# 2-PowerInput.net
KiCad netlist of a schematic drawn in Altium Designer
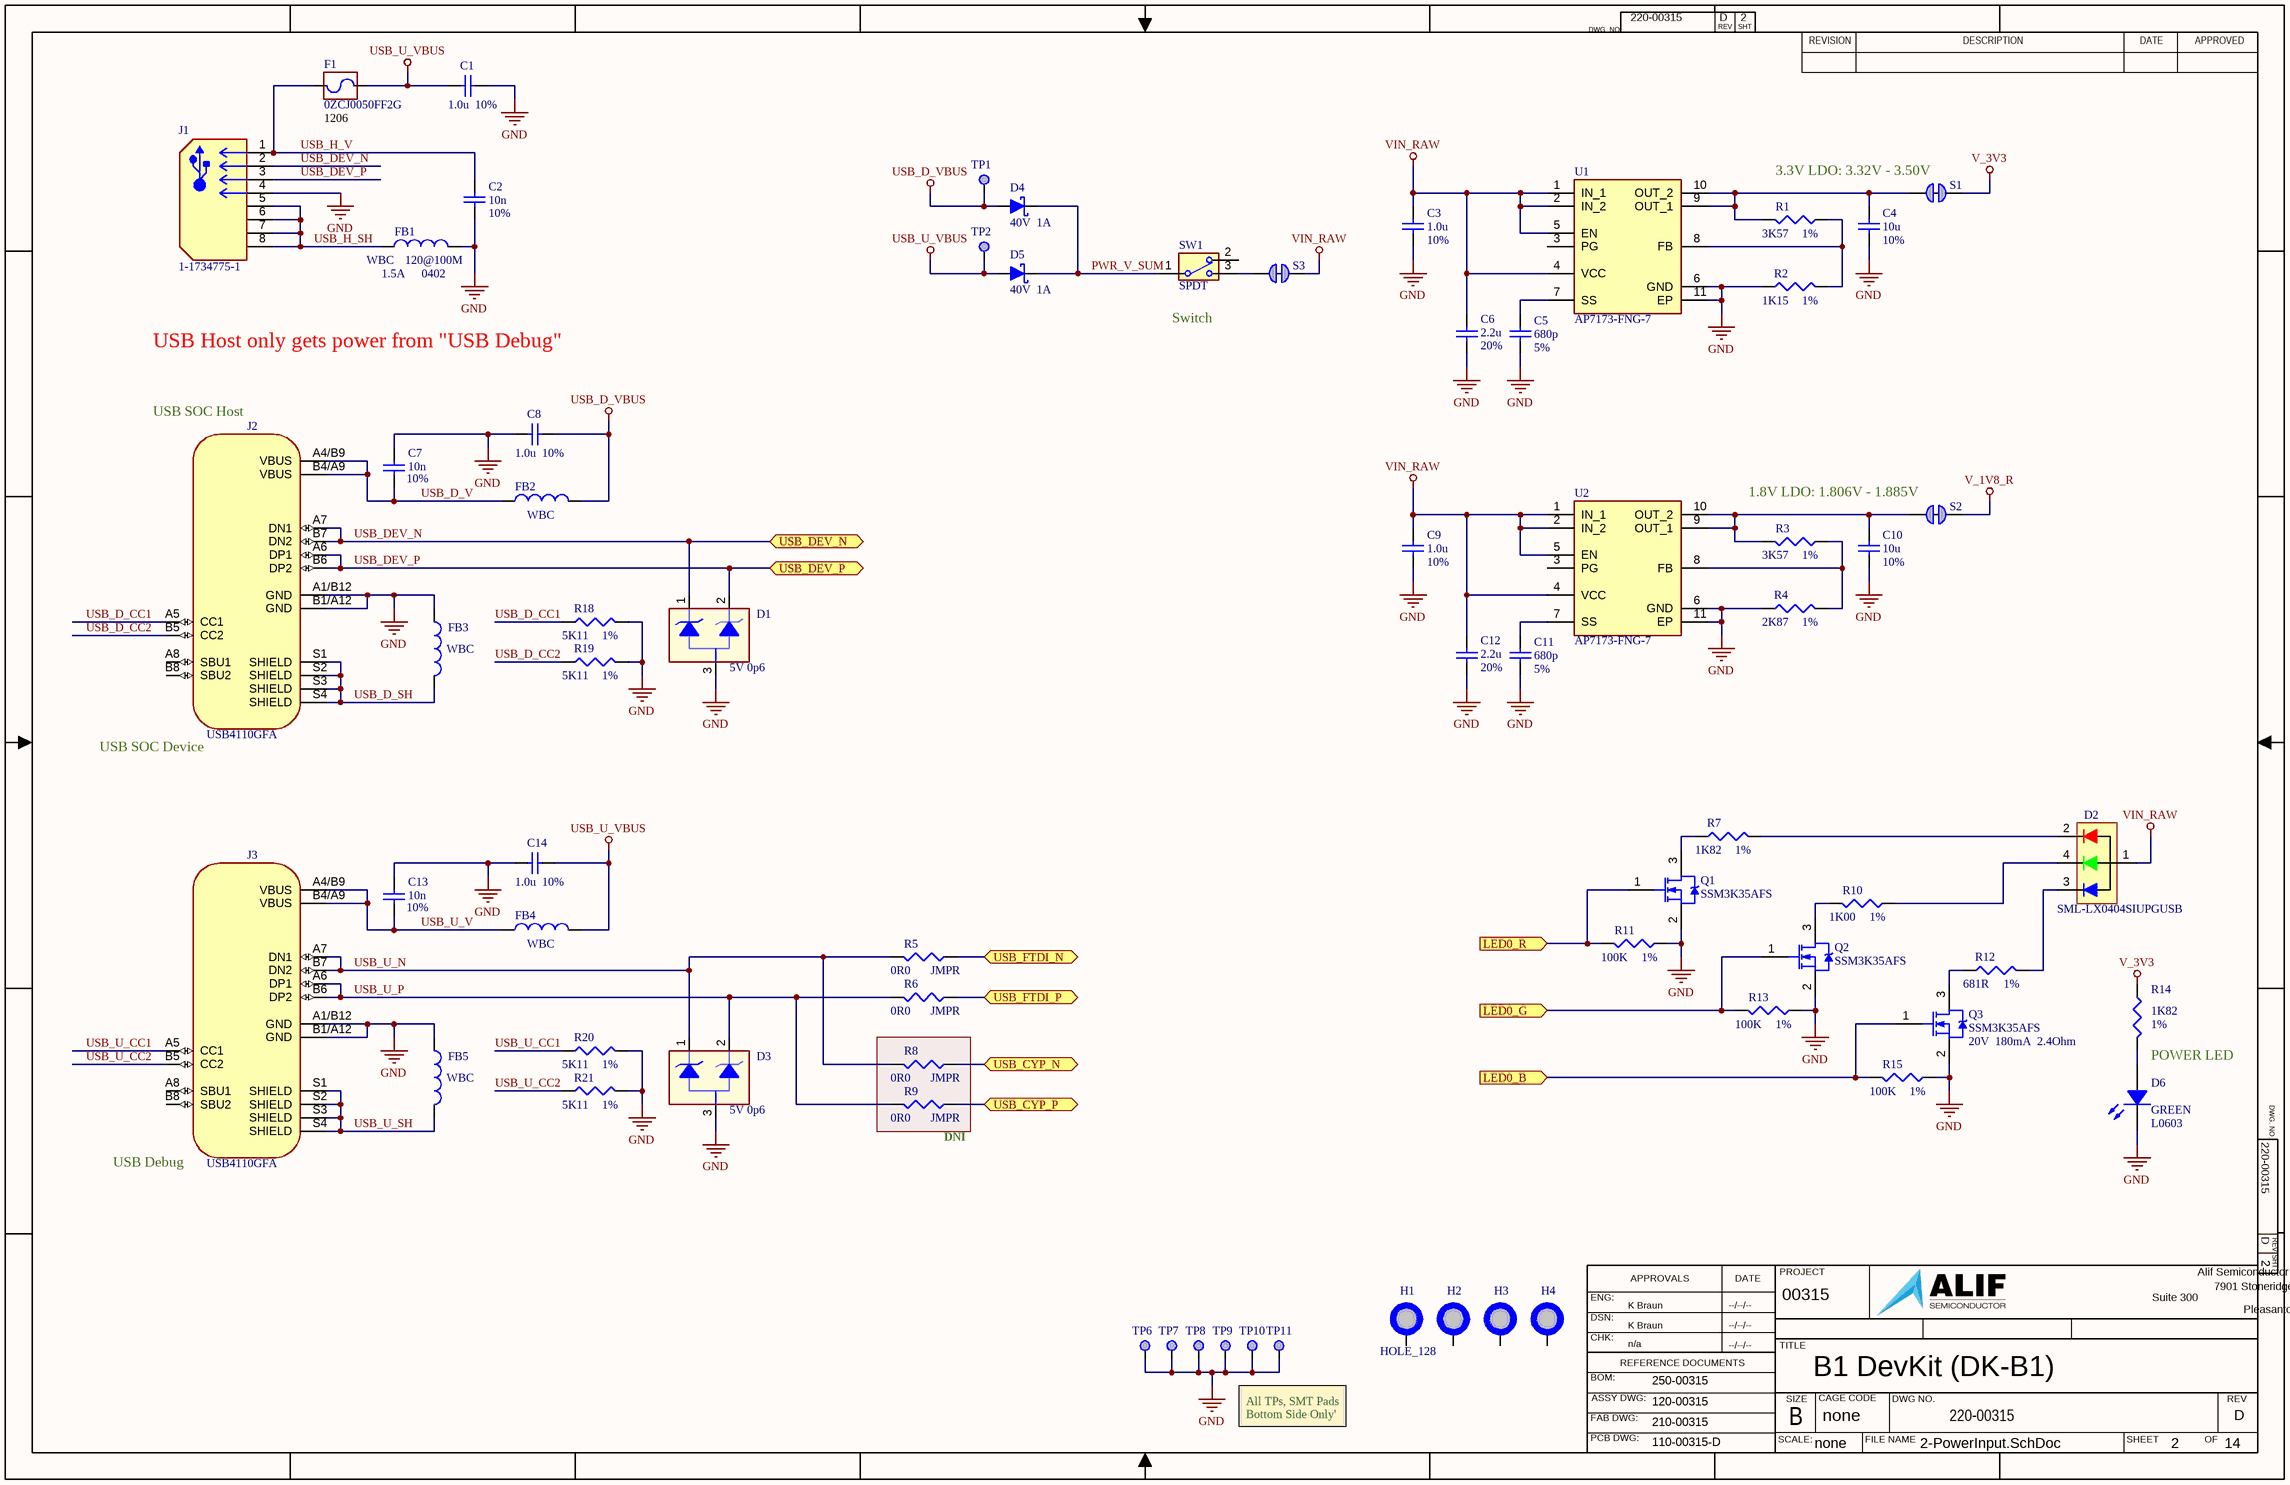
[diagram p0: 2-PowerInput.SchDoc]

(export (version "E")
  (design (tool "Eeschema 10.0.6"))
  (components
    (comp (ref "C1")
      (value "1.0u")
      (footprint "CAPC0402-01")
      (description "Cap,1.0uF,20%,25V,X5R,0402")
      (fields
        (field (name "VOLTAGE") "25V")
        (field (name "TOLERANCE") "10%")
        (field (name "Comment") "Cap")
        (field (name "PUBLISHER") "Altium Limited")
      )
      (libsource (lib "kb1") (part "Cap"))
    )
    (comp (ref "C2")
      (value "10n")
      (footprint "CAPC0402-01")
      (description "Cap,10nF,10%,50V,X7R,0402")
      (fields
        (field (name "VOLTAGE") "50V")
        (field (name "TOLERANCE") "10%")
        (field (name "Comment") "Cap")
        (field (name "PUBLISHER") "Altium Limited")
      )
      (libsource (lib "kb1") (part "Cap"))
    )
    (comp (ref "C3")
      (value "1.0u")
      (footprint "CAPC0402-01")
      (description "Cap,1.0uF,20%,25V,X5R,0402")
      (fields
        (field (name "VOLTAGE") "25V")
        (field (name "TOLERANCE") "10%")
        (field (name "Comment") "Cap")
        (field (name "PUBLISHER") "Altium Limited")
      )
      (libsource (lib "kb1") (part "Cap"))
    )
    (comp (ref "C4")
      (value "10u")
      (footprint "CAPC0402-01")
      (description "Cap,10uF,20%,10V,X5R,0402")
      (fields
        (field (name "VOLTAGE") "10V")
        (field (name "TOLERANCE") "10%")
        (field (name "Comment") "Cap")
        (field (name "PUBLISHER") "Altium Limited")
      )
      (libsource (lib "kb1") (part "Cap"))
    )
    (comp (ref "C5")
      (value "680p")
      (footprint "CAPC0402-01")
      (description "Cap,680pF,5%,50V,C0G,0402")
      (fields
        (field (name "VOLTAGE") "50V")
        (field (name "TOLERANCE") "5%")
        (field (name "Comment") "Cap")
        (field (name "PUBLISHER") "Altium Limited")
      )
      (libsource (lib "kb1") (part "Cap"))
    )
    (comp (ref "C6")
      (value "2.2u")
      (footprint "CAPC0402-01")
      (description "Cap,2.2uF,20%,25V,X5R,0402")
      (fields
        (field (name "VOLTAGE") "25V")
        (field (name "TOLERANCE") "20%")
        (field (name "Comment") "Cap_225M25VX5R0402_1")
        (field (name "PUBLISHER") "Altium Limited")
      )
      (libsource (lib "Alif-2") (part "Cap_225M25VX5R0402_1"))
    )
    (comp (ref "C7")
      (value "10n")
      (footprint "CAPC0402-01")
      (description "Cap,10nF,10%,50V,X7R,0402")
      (fields
        (field (name "VOLTAGE") "50V")
        (field (name "TOLERANCE") "10%")
        (field (name "Comment") "Cap")
        (field (name "PUBLISHER") "Altium Limited")
      )
      (libsource (lib "kb1") (part "Cap"))
    )
    (comp (ref "C8")
      (value "1.0u")
      (footprint "CAPC0402-01")
      (description "Cap,1.0uF,20%,25V,X5R,0402")
      (fields
        (field (name "VOLTAGE") "25V")
        (field (name "TOLERANCE") "10%")
        (field (name "Comment") "Cap")
        (field (name "PUBLISHER") "Altium Limited")
      )
      (libsource (lib "kb1") (part "Cap"))
    )
    (comp (ref "C9")
      (value "1.0u")
      (footprint "CAPC0402-01")
      (description "Cap,1.0uF,20%,25V,X5R,0402")
      (fields
        (field (name "VOLTAGE") "25V")
        (field (name "TOLERANCE") "10%")
        (field (name "Comment") "Cap")
        (field (name "PUBLISHER") "Altium Limited")
      )
      (libsource (lib "kb1") (part "Cap"))
    )
    (comp (ref "C10")
      (value "10u")
      (footprint "CAPC0402-01")
      (description "Cap,10uF,20%,10V,X5R,0402")
      (fields
        (field (name "VOLTAGE") "10V")
        (field (name "TOLERANCE") "10%")
        (field (name "Comment") "Cap")
        (field (name "PUBLISHER") "Altium Limited")
      )
      (libsource (lib "kb1") (part "Cap"))
    )
    (comp (ref "C11")
      (value "680p")
      (footprint "CAPC0402-01")
      (description "Cap,680pF,5%,50V,C0G,0402")
      (fields
        (field (name "VOLTAGE") "50V")
        (field (name "TOLERANCE") "5%")
        (field (name "Comment") "Cap")
        (field (name "PUBLISHER") "Altium Limited")
      )
      (libsource (lib "kb1") (part "Cap"))
    )
    (comp (ref "C12")
      (value "2.2u")
      (footprint "CAPC0402-01")
      (description "Cap,2.2uF,20%,25V,X5R,0402")
      (fields
        (field (name "VOLTAGE") "25V")
        (field (name "TOLERANCE") "20%")
        (field (name "Comment") "Cap_225M25VX5R0402_1")
        (field (name "PUBLISHER") "Altium Limited")
      )
      (libsource (lib "Alif-2") (part "Cap_225M25VX5R0402_1"))
    )
    (comp (ref "C13")
      (value "10n")
      (footprint "CAPC0402-01")
      (description "Cap,10nF,10%,50V,X7R,0402")
      (fields
        (field (name "VOLTAGE") "50V")
        (field (name "TOLERANCE") "10%")
        (field (name "Comment") "Cap")
        (field (name "PUBLISHER") "Altium Limited")
      )
      (libsource (lib "kb1") (part "Cap"))
    )
    (comp (ref "C14")
      (value "1.0u")
      (footprint "CAPC0402-01")
      (description "Cap,1.0uF,20%,25V,X5R,0402")
      (fields
        (field (name "VOLTAGE") "25V")
        (field (name "TOLERANCE") "10%")
        (field (name "Comment") "Cap")
        (field (name "PUBLISHER") "Altium Limited")
      )
      (libsource (lib "kb1") (part "Cap"))
    )
    (comp (ref "D1")
      (value "5V 0p6")
      (footprint "SOT-23_DBZ_TEX")
      (description "Diode,Zener,Dual,Common Anode")
      (fields (field (name "Comment") "Zener") (field (name "PUBLISHER") "Altium Limited"))
      (libsource (lib "Alif-2") (part "D Zener_2_ComA"))
    )
    (comp (ref "D2")
      (value "SML-LX0404SIUPGUSB")
      (footprint "LED_SML-LX0404_LUM")
      (description "Diode,LED,RGB, (@2mA) -> R=10mcd & 1.75V, G = 50mcd & 2.75V, B = 20mcd & 2.95V, 0404(1mm x 1mm)")
      (fields (field (name "PUBLISHER") "Altium Limited"))
      (libsource (lib "Alif-2") (part "D LED_RGB_CA_1MMc1MM"))
    )
    (comp (ref "D3")
      (value "5V 0p6")
      (footprint "SOT-23_DBZ_TEX")
      (description "Diode,Zener,Dual,Common Anode")
      (fields (field (name "Comment") "Zener") (field (name "PUBLISHER") "Altium Limited"))
      (libsource (lib "Alif-2") (part "D Zener_2_ComA"))
    )
    (comp (ref "D4")
      (value "40V  1A")
      (footprint "SOD123F_NXP")
      (description "Diode,Schottky,1A,40V,SOD123")
      (fields (field (name "Comment") "D Schottky") (field (name "PUBLISHER") "Altium Limited"))
      (libsource (lib "Alif-2") (part "D Schottky"))
    )
    (comp (ref "D5")
      (value "40V  1A")
      (footprint "SOD123F_NXP")
      (description "Diode,Schottky,1A,40V,SOD123")
      (fields (field (name "Comment") "D Schottky") (field (name "PUBLISHER") "Altium Limited"))
      (libsource (lib "Alif-2") (part "D Schottky"))
    )
    (comp (ref "D6")
      (value "GREEN")
      (footprint "LED_0603-GRN_AK")
      (description "Diode,LED,Green 573nm,300mcd @ 20mA,0603")
      (fields
        (field (name "PACKAGEREFERENCE") "L0603")
        (field (name "Comment") "D LED2")
        (field (name "PUBLISHER") "Altium Limited")
      )
      (libsource (lib "Alif-2") (part "D LED2"))
    )
    (comp (ref "F1")
      (value "0ZCJ0050FF2G")
      (footprint "1206")
      (description "Fuse,Poly PTC,1A,8V,150mOhm,1206")
      (fields (field (name "COPYRIGHT") "Copyright (C) 2022 Ultra Librarian. All rights reserved."))
      (libsource (lib "Alif-2") (part "Fuse_PTC_0ZCJ0050FF2G"))
    )
    (comp (ref "FB1")
      (value "WBC")
      (footprint "FB_0402_MuRata_as_R0402")
      (description "Ind,WidebandChoke,1.5A,120ohm@100MHz,95mOhm,0402")
      (fields
        (field (name "TOLERANCE") "30%")
        (field (name "IMPEDANCE") "120@100M")
        (field (name "PCB_FOOTPRINT") "0402")
        (field (name "RMS_CURRENT") "1.5A")
        (field (name "Comment") "Ind_WBC_1A5_120@100M0402_1")
        (field (name "PUBLISHER") "Altium Limited")
      )
      (libsource (lib "Alif2") (part "Ind_WBC_1A5_120@100M0402_1"))
    )
    (comp (ref "FB2")
      (value "WBC")
      (footprint "FB_0402_MuRata_as_R0402")
      (description "Ind,WidebandChoke,1.5A,120ohm@100MHz,95mOhm,0402")
      (fields
        (field (name "TOLERANCE") "30%")
        (field (name "Comment") "Ind_WBC_1A5_120@100M0402_1")
        (field (name "PUBLISHER") "Altium Limited")
      )
      (libsource (lib "Alif2") (part "Ind_WBC_1A5_120@100M0402_1"))
    )
    (comp (ref "FB3")
      (value "WBC")
      (footprint "FB_0402_MuRata_as_R0402")
      (description "Ind,WidebandChoke,1.5A,120ohm@100MHz,95mOhm,0402")
      (fields
        (field (name "TOLERANCE") "30%")
        (field (name "Comment") "Ind_WBC_1A5_120@100M0402_1")
        (field (name "PUBLISHER") "Altium Limited")
      )
      (libsource (lib "Alif2") (part "Ind_WBC_1A5_120@100M0402_1"))
    )
    (comp (ref "FB4")
      (value "WBC")
      (footprint "FB_0402_MuRata_as_R0402")
      (description "Ind,WidebandChoke,1.5A,120ohm@100MHz,95mOhm,0402")
      (fields
        (field (name "TOLERANCE") "30%")
        (field (name "Comment") "Ind_WBC_1A5_120@100M0402_1")
        (field (name "PUBLISHER") "Altium Limited")
      )
      (libsource (lib "Alif2") (part "Ind_WBC_1A5_120@100M0402_1"))
    )
    (comp (ref "FB5")
      (value "WBC")
      (footprint "FB_0402_MuRata_as_R0402")
      (description "Ind,WidebandChoke,1.5A,120ohm@100MHz,95mOhm,0402")
      (fields
        (field (name "TOLERANCE") "30%")
        (field (name "Comment") "Ind_WBC_1A5_120@100M0402_1")
        (field (name "PUBLISHER") "Altium Limited")
      )
      (libsource (lib "Alif2") (part "Ind_WBC_1A5_120@100M0402_1"))
    )
    (comp (ref "H1")
      (value "HOLE_128")
      (footprint "Hole_#4")
      (description "Hole, #4,--not a BOM item--")
      (libsource (lib "Alif-2") (part "HOLE_128"))
    )
    (comp (ref "H2")
      (value "HOLE_128")
      (footprint "Hole_#4")
      (description "Hole, #4,--not a BOM item--")
      (libsource (lib "Alif-2") (part "HOLE_128"))
    )
    (comp (ref "H3")
      (value "HOLE_128")
      (footprint "Hole_#4")
      (description "Hole, #4,--not a BOM item--")
      (libsource (lib "Alif-2") (part "HOLE_128"))
    )
    (comp (ref "H4")
      (value "HOLE_128")
      (footprint "Hole_#4")
      (description "Hole, #4,--not a BOM item--")
      (libsource (lib "Alif-2") (part "HOLE_128"))
    )
    (comp (ref "J1")
      (value "1-1734775-1")
      (footprint "614004134726")
      (description "Conn,USB 2.0, Type A Recept,4 Pos, R/A")
      (fields (field (name "COPYRIGHT") "Copyright (C) 2022 Ultra Librarian. All rights reserved."))
      (libsource (lib "Alif-2") (part "Conn_1-1734775-1"))
    )
    (comp (ref "J2")
      (value "USB4110GFA")
      (footprint "CONN_USB_C_GCT_USB4110GFA")
      (description "CONN,USB-C, USB 2.0 Receptacle Connector 24 (16+8 Dummy) Position Surface Mount, Right Angle")
      (libsource (lib "Alif-2") (part "CONN_USB_C_SMT_USB4110GFA"))
    )
    (comp (ref "J3")
      (value "USB4110GFA")
      (footprint "CONN_USB_C_GCT_USB4110GFA")
      (description "CONN,USB-C, USB 2.0 Receptacle Connector 24 (16+8 Dummy) Position Surface Mount, Right Angle")
      (libsource (lib "Alif-2") (part "CONN_USB_C_SMT_USB4110GFA"))
    )
    (comp (ref "Q1")
      (value "NMOS-2_SOT")
      (footprint "SC75_SSM_TOS-L")
      (description "MOSFET,N-CH,20V,250mA,1.1Ohm,SOT-23")
      (fields
        (field (name "MANUFACTURER PART NUMBER 1") "SSM3K35AFS")
        (field (name "PUBLISHER") "Altium Limited")
      )
      (libsource (lib "Alif-2") (part "NMOS-2_SOT"))
    )
    (comp (ref "Q2")
      (value "NMOS-2_SOT")
      (footprint "SC75_SSM_TOS-L")
      (description "MOSFET,N-CH,20V,250mA,1.1Ohm,SOT-23")
      (fields
        (field (name "MANUFACTURER PART NUMBER 1") "SSM3K35AFS")
        (field (name "PUBLISHER") "Altium Limited")
      )
      (libsource (lib "Alif-2") (part "NMOS-2_SOT"))
    )
    (comp (ref "Q3")
      (value "20V  180mA  2.4Ohm")
      (footprint "SC75_SSM_TOS-L")
      (description "MOSFET,N-CH,20V,250mA,1.1Ohm,SOT-23")
      (fields
        (field (name "MANUFACTURER PART NUMBER 1") "SSM3K35AFS")
        (field (name "Comment") "NMOS-2_SOT")
        (field (name "PUBLISHER") "Altium Limited")
      )
      (libsource (lib "Alif-2") (part "NMOS-2_SOT"))
    )
    (comp (ref "R1")
      (value "3K57")
      (footprint "RESC0402-01")
      (description "Res,3K57,1%,100ppm,0402")
      (fields
        (field (name "TOLERANCE") "1%")
        (field (name "Comment") "Res3")
        (field (name "PUBLISHER") "Altium Limited")
      )
      (libsource (lib "kb1") (part "Res3"))
    )
    (comp (ref "R2")
      (value "1K15")
      (footprint "RESC0402-01")
      (description "Res,1K15,1%,100ppm,0402")
      (fields
        (field (name "TOLERANCE") "1%")
        (field (name "Comment") "Res3")
        (field (name "PUBLISHER") "Altium Limited")
      )
      (libsource (lib "kb1") (part "Res3"))
    )
    (comp (ref "R3")
      (value "3K57")
      (footprint "RESC0402-01")
      (description "Res,3K57,1%,100ppm,0402")
      (fields
        (field (name "TOLERANCE") "1%")
        (field (name "Comment") "Res3")
        (field (name "PUBLISHER") "Altium Limited")
      )
      (libsource (lib "kb1") (part "Res3"))
    )
    (comp (ref "R4")
      (value "2K87")
      (footprint "RESC0402-01")
      (description "Res,2K87,1%,100ppm,0402")
      (fields
        (field (name "TOLERANCE") "1%")
        (field (name "Comment") "Res3")
        (field (name "PUBLISHER") "Altium Limited")
      )
      (libsource (lib "kb1") (part "Res3"))
    )
    (comp (ref "R5")
      (value "0R0")
      (footprint "RESC0402-01")
      (description "Res,0R ohm,Jumper,0402")
      (fields
        (field (name "TOLERANCE") "JMPR")
        (field (name "Comment") "Res3")
        (field (name "PUBLISHER") "Altium Limited")
      )
      (libsource (lib "kb1") (part "Res3"))
    )
    (comp (ref "R6")
      (value "0R0")
      (footprint "RESC0402-01")
      (description "Res,0R ohm,Jumper,0402")
      (fields
        (field (name "TOLERANCE") "JMPR")
        (field (name "Comment") "Res3")
        (field (name "PUBLISHER") "Altium Limited")
      )
      (libsource (lib "kb1") (part "Res3"))
    )
    (comp (ref "R7")
      (value "1K82")
      (footprint "RESC0402-01")
      (description "Res,1K82,1%,100ppm,0402")
      (fields
        (field (name "TOLERANCE") "1%")
        (field (name "Comment") "Res3")
        (field (name "PUBLISHER") "Altium Limited")
      )
      (libsource (lib "kb1") (part "Res3"))
    )
    (comp (ref "R8")
      (value "0R0")
      (footprint "RESC0402-01")
      (description "DNI,Res,0R ohm,Jumper,0402")
      (fields
        (field (name "TOLERANCE") "JMPR")
        (field (name "Comment") "Res3")
        (field (name "PUBLISHER") "Altium Limited")
      )
      (libsource (lib "kb1") (part "Res3"))
    )
    (comp (ref "R9")
      (value "0R0")
      (footprint "RESC0402-01")
      (description "DNI,Res,0R ohm,Jumper,0402")
      (fields
        (field (name "TOLERANCE") "JMPR")
        (field (name "Comment") "Res3")
        (field (name "PUBLISHER") "Altium Limited")
      )
      (libsource (lib "kb1") (part "Res3"))
    )
    (comp (ref "R10")
      (value "1K00")
      (footprint "RESC0402-01")
      (description "Res,1K00,1%,100ppm,0402")
      (fields
        (field (name "TOLERANCE") "1%")
        (field (name "Comment") "Res3")
        (field (name "PUBLISHER") "Altium Limited")
      )
      (libsource (lib "kb1") (part "Res3"))
    )
    (comp (ref "R11")
      (value "100K")
      (footprint "RESC0402-01")
      (description "Res,100K,1%,100ppm,0402")
      (fields
        (field (name "TOLERANCE") "1%")
        (field (name "Comment") "Res3")
        (field (name "PUBLISHER") "Altium Limited")
      )
      (libsource (lib "kb1") (part "Res3"))
    )
    (comp (ref "R12")
      (value "681R")
      (footprint "RESC0402-01")
      (description "Res,681R,1%,100ppm,0402")
      (fields
        (field (name "TOLERANCE") "1%")
        (field (name "Comment") "Res3")
        (field (name "PUBLISHER") "Altium Limited")
      )
      (libsource (lib "kb1") (part "Res3"))
    )
    (comp (ref "R13")
      (value "100K")
      (footprint "RESC0402-01")
      (description "Res,100K,1%,100ppm,0402")
      (fields
        (field (name "TOLERANCE") "1%")
        (field (name "Comment") "Res3")
        (field (name "PUBLISHER") "Altium Limited")
      )
      (libsource (lib "kb1") (part "Res3"))
    )
    (comp (ref "R14")
      (value "1K82")
      (footprint "RESC0402-01")
      (description "Res,1K82,1%,100ppm,0402")
      (fields
        (field (name "TOLERANCE") "1%")
        (field (name "Comment") "Res3")
        (field (name "PUBLISHER") "Altium Limited")
      )
      (libsource (lib "kb1") (part "Res3"))
    )
    (comp (ref "R15")
      (value "100K")
      (footprint "RESC0402-01")
      (description "Res,100K,1%,100ppm,0402")
      (fields
        (field (name "TOLERANCE") "1%")
        (field (name "Comment") "Res3")
        (field (name "PUBLISHER") "Altium Limited")
      )
      (libsource (lib "kb1") (part "Res3"))
    )
    (comp (ref "R18")
      (value "5K11")
      (footprint "RESC0402-01")
      (description "Res,5K11,1%,100ppm,0402")
      (fields
        (field (name "TOLERANCE") "1%")
        (field (name "Comment") "Res3")
        (field (name "PUBLISHER") "Altium Limited")
      )
      (libsource (lib "kb1") (part "Res3"))
    )
    (comp (ref "R19")
      (value "5K11")
      (footprint "RESC0402-01")
      (description "Res,5K11,1%,100ppm,0402")
      (fields
        (field (name "TOLERANCE") "1%")
        (field (name "Comment") "Res3")
        (field (name "PUBLISHER") "Altium Limited")
      )
      (libsource (lib "kb1") (part "Res3"))
    )
    (comp (ref "R20")
      (value "5K11")
      (footprint "RESC0402-01")
      (description "Res,5K11,1%,100ppm,0402")
      (fields
        (field (name "TOLERANCE") "1%")
        (field (name "Comment") "Res3")
        (field (name "PUBLISHER") "Altium Limited")
      )
      (libsource (lib "kb1") (part "Res3"))
    )
    (comp (ref "R21")
      (value "5K11")
      (footprint "RESC0402-01")
      (description "Res,5K11,1%,100ppm,0402")
      (fields
        (field (name "TOLERANCE") "1%")
        (field (name "Comment") "Res3")
        (field (name "PUBLISHER") "Altium Limited")
      )
      (libsource (lib "kb1") (part "Res3"))
    )
    (comp (ref "S1")
      (value "SolderJumperShorted_Small")
      (footprint "Solderbridge_Shorted")
      (description "DNI,Solderable Jumper,Shorted")
      (fields (field (name "PUBLISHER") "Altium Limited"))
      (libsource (lib "Alif-2") (part "SolderJumperShorted_Small"))
    )
    (comp (ref "S2")
      (value "SolderJumperShorted_Small")
      (footprint "Solderbridge_Shorted")
      (description "DNI,Solderable Jumper,Shorted")
      (fields (field (name "PUBLISHER") "Altium Limited"))
      (libsource (lib "Alif-2") (part "SolderJumperShorted_Small"))
    )
    (comp (ref "S3")
      (value "SolderJumperShorted_Small")
      (footprint "Solderbridge_Shorted")
      (description "DNI,Solderable Jumper,Shorted")
      (fields (field (name "PUBLISHER") "Altium Limited"))
      (libsource (lib "Alif-2") (part "SolderJumperShorted_Small"))
    )
    (comp (ref "SW1")
      (value "SPDT")
      (footprint "SW_450301014042_WRE")
      (description "Switch,SPDT, 12V, 500mA, Non-Shorting, 3 Pin PCB Vertical")
      (fields (field (name "PUBLISHER") "Altium Limited"))
      (libsource (lib "Alif-2") (part "SW-SPDT_Vert-3P"))
    )
    (comp (ref "TP1")
      (value "TP_SMPAD")
      (footprint "TP_30_RND")
      (description "Test Point, SMT Pad,--not a BOM item--")
      (libsource (lib "Alif-2") (part "TP_SMPAD"))
    )
    (comp (ref "TP2")
      (value "TP_SMPAD")
      (footprint "TP_30_RND")
      (description "Test Point, SMT Pad,--not a BOM item--")
      (libsource (lib "Alif-2") (part "TP_SMPAD"))
    )
    (comp (ref "TP6")
      (value "TP_SMPAD")
      (footprint "TP_30_RND")
      (description "Test Point, SMT Pad,--not a BOM item--")
      (libsource (lib "Alif-2") (part "TP_SMPAD"))
    )
    (comp (ref "TP7")
      (value "TP_SMPAD")
      (footprint "TP_30_RND")
      (description "Test Point, SMT Pad,--not a BOM item--")
      (libsource (lib "Alif-2") (part "TP_SMPAD"))
    )
    (comp (ref "TP8")
      (value "TP_SMPAD")
      (footprint "TP_30_RND")
      (description "Test Point, SMT Pad,--not a BOM item--")
      (libsource (lib "Alif-2") (part "TP_SMPAD"))
    )
    (comp (ref "TP9")
      (value "TP_SMPAD")
      (footprint "TP_30_RND")
      (description "Test Point, SMT Pad,--not a BOM item--")
      (libsource (lib "Alif-2") (part "TP_SMPAD"))
    )
    (comp (ref "TP10")
      (value "TP_SMPAD")
      (footprint "TP_30_RND")
      (description "Test Point, SMT Pad,--not a BOM item--")
      (libsource (lib "Alif-2") (part "TP_SMPAD"))
    )
    (comp (ref "TP11")
      (value "TP_SMPAD")
      (footprint "TP_30_RND")
      (description "Test Point, SMT Pad,--not a BOM item--")
      (libsource (lib "Alif-2") (part "TP_SMPAD"))
    )
    (comp (ref "U1")
      (value "AP7173-FNG-7")
      (footprint "UDFN3030-10_SON50P300X300X63-11N")
      (description "IC, LDO,Adj 0.8V - 3.3V,1.5A,UDFN3030-10")
      (libsource (lib "Alif-2") (part "IC_LDO_AP7173-FNG-7"))
    )
    (comp (ref "U2")
      (value "AP7173-FNG-7")
      (footprint "UDFN3030-10_SON50P300X300X63-11N")
      (description "IC, LDO,Adj 0.8V - 3.3V,1.5A,UDFN3030-10")
      (libsource (lib "Alif-2") (part "IC_LDO_AP7173-FNG-7"))
    )
  )
  (nets
    (net (code "1") (name "/LED0_B") (class "Default")
      (node (ref "Q3") (pin "1") (pinfunction "G_1") (pintype "passive"))
      (node (ref "R15") (pin "2") (pinfunction "2_2") (pintype "passive"))
    )
    (net (code "2") (name "/LED0_G") (class "Default")
      (node (ref "Q2") (pin "1") (pinfunction "G_1") (pintype "passive"))
      (node (ref "R13") (pin "2") (pinfunction "2_2") (pintype "passive"))
    )
    (net (code "3") (name "/LED0_R") (class "Default")
      (node (ref "Q1") (pin "1") (pinfunction "G_1") (pintype "passive"))
      (node (ref "R11") (pin "2") (pinfunction "2_2") (pintype "passive"))
    )
    (net (code "4") (name "/PWR_V_SUM") (class "Default")
      (node (ref "D4") (pin "1") (pinfunction "K_1") (pintype "passive"))
      (node (ref "D5") (pin "1") (pinfunction "K_1") (pintype "passive"))
      (node (ref "SW1") (pin "1") (pinfunction "COMMON_1") (pintype "passive"))
    )
    (net (code "5") (name "/USB_CYP_N") (class "Default")
      (node (ref "R8") (pin "1") (pinfunction "1_1") (pintype "passive"))
    )
    (net (code "6") (name "/USB_CYP_P") (class "Default")
      (node (ref "R9") (pin "1") (pinfunction "1_1") (pintype "passive"))
    )
    (net (code "7") (name "/USB_DEV_N") (class "Default")
      (node (ref "D1") (pin "1") (pinfunction "K1_1") (pintype "passive"))
      (node (ref "J1") (pin "2") (pinfunction "2_2") (pintype "passive"))
      (node (ref "J2") (pin "A7") (pinfunction "DN1_A7") (pintype "bidirectional"))
      (node (ref "J2") (pin "B7") (pinfunction "DN2_B7") (pintype "bidirectional"))
    )
    (net (code "8") (name "/USB_DEV_P") (class "Default")
      (node (ref "D1") (pin "2") (pinfunction "2_2") (pintype "passive"))
      (node (ref "J1") (pin "3") (pinfunction "3_3") (pintype "passive"))
      (node (ref "J2") (pin "A6") (pinfunction "DP1_A6") (pintype "bidirectional"))
      (node (ref "J2") (pin "B6") (pinfunction "DP2_B6") (pintype "bidirectional"))
    )
    (net (code "9") (name "/USB_D_CC1") (class "Default")
      (node (ref "J2") (pin "A5") (pinfunction "CC1_A5") (pintype "bidirectional"))
      (node (ref "R18") (pin "1") (pinfunction "1_1") (pintype "passive"))
    )
    (net (code "10") (name "/USB_D_CC2") (class "Default")
      (node (ref "J2") (pin "B5") (pinfunction "CC2_B5") (pintype "bidirectional"))
      (node (ref "R19") (pin "1") (pinfunction "1_1") (pintype "passive"))
    )
    (net (code "11") (name "/USB_D_SH") (class "Default")
      (node (ref "FB3") (pin "2") (pinfunction "2_2") (pintype "passive"))
      (node (ref "J2") (pin "S1") (pinfunction "SHIELD_S1") (pintype "power_in"))
      (node (ref "J2") (pin "S2") (pinfunction "SHIELD_S2") (pintype "power_in"))
      (node (ref "J2") (pin "S3") (pinfunction "SHIELD_S3") (pintype "power_in"))
      (node (ref "J2") (pin "S4") (pinfunction "SHIELD_S4") (pintype "power_in"))
    )
    (net (code "12") (name "/USB_D_V") (class "Default")
      (node (ref "C7") (pin "2") (pinfunction "2_2") (pintype "passive"))
      (node (ref "FB2") (pin "1") (pinfunction "1_1") (pintype "passive"))
      (node (ref "J2") (pin "A4/B9") (pinfunction "VBUS_A4/B9") (pintype "power_in"))
      (node (ref "J2") (pin "B4/A9") (pinfunction "VBUS_B4/A9") (pintype "power_in"))
    )
    (net (code "13") (name "/USB_FTDI_N") (class "Default")
      (node (ref "R5") (pin "1") (pinfunction "1_1") (pintype "passive"))
    )
    (net (code "14") (name "/USB_FTDI_P") (class "Default")
      (node (ref "R6") (pin "1") (pinfunction "1_1") (pintype "passive"))
    )
    (net (code "15") (name "/USB_H_SH") (class "Default")
      (node (ref "FB1") (pin "1") (pinfunction "1_1") (pintype "passive"))
      (node (ref "J1") (pin "5") (pinfunction "5_5") (pintype "passive"))
      (node (ref "J1") (pin "6") (pinfunction "6_6") (pintype "passive"))
      (node (ref "J1") (pin "7") (pinfunction "7_7") (pintype "passive"))
      (node (ref "J1") (pin "8") (pinfunction "8_8") (pintype "passive"))
    )
    (net (code "16") (name "/USB_H_V") (class "Default")
      (node (ref "C2") (pin "2") (pinfunction "2_2") (pintype "passive"))
      (node (ref "F1") (pin "1") (pinfunction "1_1") (pintype "passive"))
      (node (ref "J1") (pin "1") (pinfunction "1_1") (pintype "passive"))
    )
    (net (code "17") (name "/USB_U_CC1") (class "Default")
      (node (ref "J3") (pin "A5") (pinfunction "CC1_A5") (pintype "bidirectional"))
      (node (ref "R20") (pin "1") (pinfunction "1_1") (pintype "passive"))
    )
    (net (code "18") (name "/USB_U_CC2") (class "Default")
      (node (ref "J3") (pin "B5") (pinfunction "CC2_B5") (pintype "bidirectional"))
      (node (ref "R21") (pin "1") (pinfunction "1_1") (pintype "passive"))
    )
    (net (code "19") (name "/USB_U_N") (class "Default")
      (node (ref "D3") (pin "1") (pinfunction "K1_1") (pintype "passive"))
      (node (ref "J3") (pin "A7") (pinfunction "DN1_A7") (pintype "bidirectional"))
      (node (ref "J3") (pin "B7") (pinfunction "DN2_B7") (pintype "bidirectional"))
      (node (ref "R5") (pin "2") (pinfunction "2_2") (pintype "passive"))
      (node (ref "R8") (pin "2") (pinfunction "2_2") (pintype "passive"))
    )
    (net (code "20") (name "/USB_U_P") (class "Default")
      (node (ref "D3") (pin "2") (pinfunction "2_2") (pintype "passive"))
      (node (ref "J3") (pin "A6") (pinfunction "DP1_A6") (pintype "bidirectional"))
      (node (ref "J3") (pin "B6") (pinfunction "DP2_B6") (pintype "bidirectional"))
      (node (ref "R6") (pin "2") (pinfunction "2_2") (pintype "passive"))
      (node (ref "R9") (pin "2") (pinfunction "2_2") (pintype "passive"))
    )
    (net (code "21") (name "/USB_U_SH") (class "Default")
      (node (ref "FB5") (pin "2") (pinfunction "2_2") (pintype "passive"))
      (node (ref "J3") (pin "S1") (pinfunction "SHIELD_S1") (pintype "power_in"))
      (node (ref "J3") (pin "S2") (pinfunction "SHIELD_S2") (pintype "power_in"))
      (node (ref "J3") (pin "S3") (pinfunction "SHIELD_S3") (pintype "power_in"))
      (node (ref "J3") (pin "S4") (pinfunction "SHIELD_S4") (pintype "power_in"))
    )
    (net (code "22") (name "/USB_U_V") (class "Default")
      (node (ref "C13") (pin "2") (pinfunction "2_2") (pintype "passive"))
      (node (ref "FB4") (pin "1") (pinfunction "1_1") (pintype "passive"))
      (node (ref "J3") (pin "A4/B9") (pinfunction "VBUS_A4/B9") (pintype "power_in"))
      (node (ref "J3") (pin "B4/A9") (pinfunction "VBUS_B4/A9") (pintype "power_in"))
    )
    (net (code "23") (name "GND") (class "Default")
      (node (ref "C1") (pin "2") (pinfunction "2_2") (pintype "passive"))
      (node (ref "C10") (pin "1") (pinfunction "1_1") (pintype "passive"))
      (node (ref "C11") (pin "1") (pinfunction "1_1") (pintype "passive"))
      (node (ref "C12") (pin "1") (pinfunction "1_1") (pintype "passive"))
      (node (ref "C13") (pin "1") (pinfunction "1_1") (pintype "passive"))
      (node (ref "C14") (pin "1") (pinfunction "1_1") (pintype "passive"))
      (node (ref "C2") (pin "1") (pinfunction "1_1") (pintype "passive"))
      (node (ref "C3") (pin "1") (pinfunction "1_1") (pintype "passive"))
      (node (ref "C4") (pin "1") (pinfunction "1_1") (pintype "passive"))
      (node (ref "C5") (pin "1") (pinfunction "1_1") (pintype "passive"))
      (node (ref "C6") (pin "1") (pinfunction "1_1") (pintype "passive"))
      (node (ref "C7") (pin "1") (pinfunction "1_1") (pintype "passive"))
      (node (ref "C8") (pin "1") (pinfunction "1_1") (pintype "passive"))
      (node (ref "C9") (pin "1") (pinfunction "1_1") (pintype "passive"))
      (node (ref "D1") (pin "3") (pinfunction "A_3") (pintype "passive"))
      (node (ref "D3") (pin "3") (pinfunction "A_3") (pintype "passive"))
      (node (ref "D6") (pin "K") (pinfunction "K_K") (pintype "passive"))
      (node (ref "FB1") (pin "2") (pinfunction "2_2") (pintype "passive"))
      (node (ref "FB3") (pin "1") (pinfunction "1_1") (pintype "passive"))
      (node (ref "FB5") (pin "1") (pinfunction "1_1") (pintype "passive"))
      (node (ref "J1") (pin "4") (pinfunction "4_4") (pintype "passive"))
      (node (ref "J2") (pin "A1/B12") (pinfunction "GND_A1/B12") (pintype "power_in"))
      (node (ref "J2") (pin "B1/A12") (pinfunction "GND_B1/A12") (pintype "power_in"))
      (node (ref "J3") (pin "A1/B12") (pinfunction "GND_A1/B12") (pintype "power_in"))
      (node (ref "J3") (pin "B1/A12") (pinfunction "GND_B1/A12") (pintype "power_in"))
      (node (ref "Q1") (pin "2") (pinfunction "S_2") (pintype "passive"))
      (node (ref "Q2") (pin "2") (pinfunction "S_2") (pintype "passive"))
      (node (ref "Q3") (pin "2") (pinfunction "S_2") (pintype "passive"))
      (node (ref "R11") (pin "1") (pinfunction "1_1") (pintype "passive"))
      (node (ref "R13") (pin "1") (pinfunction "1_1") (pintype "passive"))
      (node (ref "R15") (pin "1") (pinfunction "1_1") (pintype "passive"))
      (node (ref "R18") (pin "2") (pinfunction "2_2") (pintype "passive"))
      (node (ref "R19") (pin "2") (pinfunction "2_2") (pintype "passive"))
      (node (ref "R2") (pin "1") (pinfunction "1_1") (pintype "passive"))
      (node (ref "R20") (pin "2") (pinfunction "2_2") (pintype "passive"))
      (node (ref "R21") (pin "2") (pinfunction "2_2") (pintype "passive"))
      (node (ref "R4") (pin "1") (pinfunction "1_1") (pintype "passive"))
      (node (ref "TP10") (pin "1") (pinfunction "1_1") (pintype "passive"))
      (node (ref "TP11") (pin "1") (pinfunction "1_1") (pintype "passive"))
      (node (ref "TP6") (pin "1") (pinfunction "1_1") (pintype "passive"))
      (node (ref "TP7") (pin "1") (pinfunction "1_1") (pintype "passive"))
      (node (ref "TP8") (pin "1") (pinfunction "1_1") (pintype "passive"))
      (node (ref "TP9") (pin "1") (pinfunction "1_1") (pintype "passive"))
      (node (ref "U1") (pin "11") (pinfunction "EP_11") (pintype "passive"))
      (node (ref "U1") (pin "6") (pinfunction "GND_6") (pintype "passive"))
      (node (ref "U2") (pin "11") (pinfunction "EP_11") (pintype "passive"))
      (node (ref "U2") (pin "6") (pinfunction "GND_6") (pintype "passive"))
    )
    (net (code "24") (name "Net-(D2-BK)") (class "Default")
      (node (ref "D2") (pin "3") (pinfunction "BK_3") (pintype "passive"))
      (node (ref "R12") (pin "2") (pinfunction "2_2") (pintype "passive"))
    )
    (net (code "25") (name "Net-(D2-GK)") (class "Default")
      (node (ref "D2") (pin "4") (pinfunction "GK_4") (pintype "passive"))
      (node (ref "R10") (pin "1") (pinfunction "1_1") (pintype "passive"))
    )
    (net (code "26") (name "Net-(D2-RK)") (class "Default")
      (node (ref "D2") (pin "2") (pinfunction "RK_2") (pintype "passive"))
      (node (ref "R7") (pin "2") (pinfunction "2_2") (pintype "passive"))
    )
    (net (code "27") (name "Net-(D6-PadA)") (class "Default")
      (node (ref "D6") (pin "A") (pinfunction "A_A") (pintype "passive"))
      (node (ref "R14") (pin "2") (pinfunction "2_2") (pintype "passive"))
    )
    (net (code "28") (name "Net-(Q1-D)") (class "Default")
      (node (ref "Q1") (pin "3") (pinfunction "D_3") (pintype "passive"))
      (node (ref "R7") (pin "1") (pinfunction "1_1") (pintype "passive"))
    )
    (net (code "29") (name "Net-(Q2-D)") (class "Default")
      (node (ref "Q2") (pin "3") (pinfunction "D_3") (pintype "passive"))
      (node (ref "R10") (pin "2") (pinfunction "2_2") (pintype "passive"))
    )
    (net (code "30") (name "Net-(Q3-D)") (class "Default")
      (node (ref "Q3") (pin "3") (pinfunction "D_3") (pintype "passive"))
      (node (ref "R12") (pin "1") (pinfunction "1_1") (pintype "passive"))
    )
    (net (code "31") (name "Net-(SW1-NO)") (class "Default")
      (node (ref "S3") (pin "1") (pinfunction "1_1") (pintype "passive"))
      (node (ref "SW1") (pin "3") (pinfunction "NO_3") (pintype "passive"))
    )
    (net (code "32") (name "Net-(U1-FB)") (class "Default")
      (node (ref "R1") (pin "1") (pinfunction "1_1") (pintype "passive"))
      (node (ref "R2") (pin "2") (pinfunction "2_2") (pintype "passive"))
      (node (ref "U1") (pin "8") (pinfunction "FB_8") (pintype "passive"))
    )
    (net (code "33") (name "Net-(U1-OUT_1)") (class "Default")
      (node (ref "C4") (pin "2") (pinfunction "2_2") (pintype "passive"))
      (node (ref "R1") (pin "2") (pinfunction "2_2") (pintype "passive"))
      (node (ref "S1") (pin "1") (pinfunction "1_1") (pintype "passive"))
      (node (ref "U1") (pin "10") (pinfunction "OUT_2_10") (pintype "passive"))
      (node (ref "U1") (pin "9") (pinfunction "OUT_1_9") (pintype "passive"))
    )
    (net (code "34") (name "Net-(U1-SS)") (class "Default")
      (node (ref "C5") (pin "2") (pinfunction "2_2") (pintype "passive"))
      (node (ref "U1") (pin "7") (pinfunction "SS_7") (pintype "passive"))
    )
    (net (code "35") (name "Net-(U2-FB)") (class "Default")
      (node (ref "R3") (pin "1") (pinfunction "1_1") (pintype "passive"))
      (node (ref "R4") (pin "2") (pinfunction "2_2") (pintype "passive"))
      (node (ref "U2") (pin "8") (pinfunction "FB_8") (pintype "passive"))
    )
    (net (code "36") (name "Net-(U2-OUT_1)") (class "Default")
      (node (ref "C10") (pin "2") (pinfunction "2_2") (pintype "passive"))
      (node (ref "R3") (pin "2") (pinfunction "2_2") (pintype "passive"))
      (node (ref "S2") (pin "1") (pinfunction "1_1") (pintype "passive"))
      (node (ref "U2") (pin "10") (pinfunction "OUT_2_10") (pintype "passive"))
      (node (ref "U2") (pin "9") (pinfunction "OUT_1_9") (pintype "passive"))
    )
    (net (code "37") (name "Net-(U2-SS)") (class "Default")
      (node (ref "C11") (pin "2") (pinfunction "2_2") (pintype "passive"))
      (node (ref "U2") (pin "7") (pinfunction "SS_7") (pintype "passive"))
    )
    (net (code "38") (name "USB_D_VBUS") (class "Default")
      (node (ref "C8") (pin "2") (pinfunction "2_2") (pintype "passive"))
      (node (ref "D4") (pin "2") (pinfunction "A_2") (pintype "passive"))
      (node (ref "FB2") (pin "2") (pinfunction "2_2") (pintype "passive"))
      (node (ref "TP1") (pin "1") (pinfunction "1_1") (pintype "passive"))
    )
    (net (code "39") (name "USB_U_VBUS") (class "Default")
      (node (ref "C1") (pin "1") (pinfunction "1_1") (pintype "passive"))
      (node (ref "C14") (pin "2") (pinfunction "2_2") (pintype "passive"))
      (node (ref "D5") (pin "2") (pinfunction "A_2") (pintype "passive"))
      (node (ref "F1") (pin "2") (pinfunction "2_2") (pintype "passive"))
      (node (ref "FB4") (pin "2") (pinfunction "2_2") (pintype "passive"))
      (node (ref "TP2") (pin "1") (pinfunction "1_1") (pintype "passive"))
    )
    (net (code "40") (name "VIN_RAW") (class "Default")
      (node (ref "C12") (pin "2") (pinfunction "2_2") (pintype "passive"))
      (node (ref "C3") (pin "2") (pinfunction "2_2") (pintype "passive"))
      (node (ref "C6") (pin "2") (pinfunction "2_2") (pintype "passive"))
      (node (ref "C9") (pin "2") (pinfunction "2_2") (pintype "passive"))
      (node (ref "D2") (pin "1") (pinfunction "A_1") (pintype "passive"))
      (node (ref "S3") (pin "2") (pinfunction "2_2") (pintype "passive"))
      (node (ref "U1") (pin "1") (pinfunction "IN_1_1") (pintype "passive"))
      (node (ref "U1") (pin "2") (pinfunction "IN_2_2") (pintype "passive"))
      (node (ref "U1") (pin "4") (pinfunction "VCC_4") (pintype "passive"))
      (node (ref "U1") (pin "5") (pinfunction "EN_5") (pintype "passive"))
      (node (ref "U2") (pin "1") (pinfunction "IN_1_1") (pintype "passive"))
      (node (ref "U2") (pin "2") (pinfunction "IN_2_2") (pintype "passive"))
      (node (ref "U2") (pin "4") (pinfunction "VCC_4") (pintype "passive"))
      (node (ref "U2") (pin "5") (pinfunction "EN_5") (pintype "passive"))
    )
    (net (code "41") (name "V_1V8_R") (class "Default")
      (node (ref "S2") (pin "2") (pinfunction "2_2") (pintype "passive"))
    )
    (net (code "42") (name "V_3V3") (class "Default")
      (node (ref "R14") (pin "1") (pinfunction "1_1") (pintype "passive"))
      (node (ref "S1") (pin "2") (pinfunction "2_2") (pintype "passive"))
    )
    (net (code "43") (name "unconnected-(H1-Pad1)") (class "Default")
      (node (ref "H1") (pin "1") (pinfunction "1_1") (pintype "passive"))
    )
    (net (code "44") (name "unconnected-(H2-Pad1)") (class "Default")
      (node (ref "H2") (pin "1") (pinfunction "1_1") (pintype "passive"))
    )
    (net (code "45") (name "unconnected-(H3-Pad1)") (class "Default")
      (node (ref "H3") (pin "1") (pinfunction "1_1") (pintype "passive"))
    )
    (net (code "46") (name "unconnected-(H4-Pad1)") (class "Default")
      (node (ref "H4") (pin "1") (pinfunction "1_1") (pintype "passive"))
    )
    (net (code "47") (name "unconnected-(J2-SBU1-PadA8)") (class "Default")
      (node (ref "J2") (pin "A8") (pinfunction "SBU1_A8") (pintype "bidirectional"))
    )
    (net (code "48") (name "unconnected-(J2-SBU2-PadB8)") (class "Default")
      (node (ref "J2") (pin "B8") (pinfunction "SBU2_B8") (pintype "bidirectional"))
    )
    (net (code "49") (name "unconnected-(J3-SBU1-PadA8)") (class "Default")
      (node (ref "J3") (pin "A8") (pinfunction "SBU1_A8") (pintype "bidirectional"))
    )
    (net (code "50") (name "unconnected-(J3-SBU2-PadB8)") (class "Default")
      (node (ref "J3") (pin "B8") (pinfunction "SBU2_B8") (pintype "bidirectional"))
    )
    (net (code "51") (name "unconnected-(SW1-NC-Pad2)") (class "Default")
      (node (ref "SW1") (pin "2") (pinfunction "NC_2") (pintype "passive"))
    )
    (net (code "52") (name "unconnected-(U1-PG-Pad3)") (class "Default")
      (node (ref "U1") (pin "3") (pinfunction "PG_3") (pintype "passive"))
    )
    (net (code "53") (name "unconnected-(U2-PG-Pad3)") (class "Default")
      (node (ref "U2") (pin "3") (pinfunction "PG_3") (pintype "passive"))
    )
  )
)
